# FA.net
KiCad netlist of a schematic drawn in EAGLE
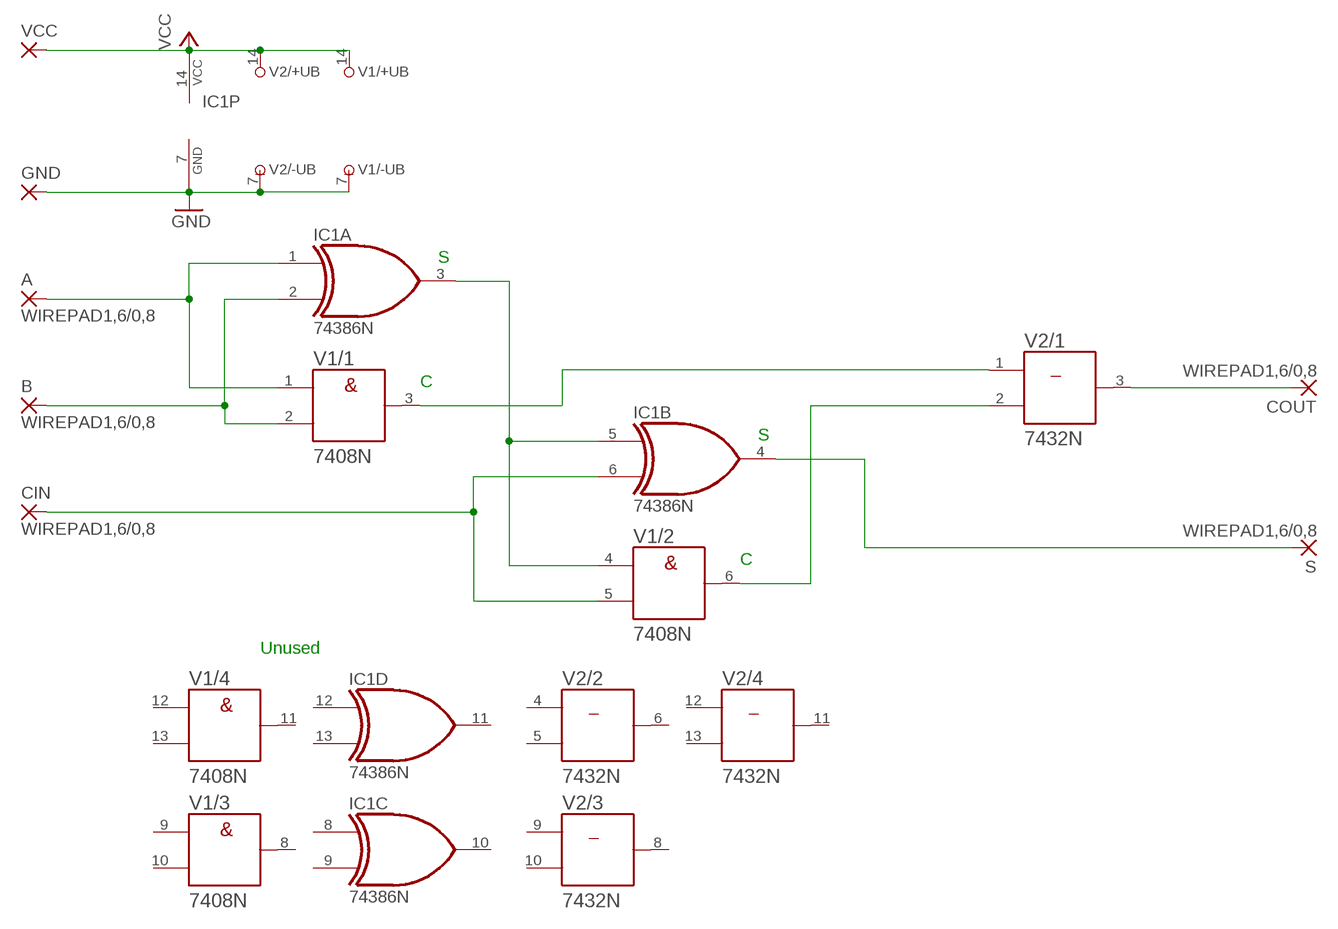
[diagram p0: schematic, sheet 1]

(export (version "E")
  (design (tool "Eeschema 10.0.6"))
  (components
    (comp (ref "A")
      (value "WIREPAD1,6/0,8")
      (footprint "eagle-import:1,6_0,8")
      (libsource (lib "eagle-import") (part "WIREPAD1,6/0,8"))
    )
    (comp (ref "B")
      (value "WIREPAD1,6/0,8")
      (footprint "eagle-import:1,6_0,8")
      (libsource (lib "eagle-import") (part "WIREPAD1,6/0,8"))
    )
    (comp (ref "CIN")
      (value "WIREPAD1,6/0,8")
      (footprint "eagle-import:1,6_0,8")
      (libsource (lib "eagle-import") (part "WIREPAD1,6/0,8"))
    )
    (comp (ref "COUT")
      (value "WIREPAD1,6/0,8")
      (footprint "eagle-import:1,6_0,8")
      (libsource (lib "eagle-import") (part "WIREPAD1,6/0,8"))
    )
    (comp (ref "GND")
      (value "1,6/0,8")
      (footprint "eagle-import:1,6_0,8")
      (libsource (lib "eagle-import") (part "1,6/0,8"))
    )
    (comp (ref "IC1")
      (value "74386N")
      (footprint "eagle-import:DIL14")
      (libsource (lib "eagle-import") (part "74386N"))
    )
    (comp (ref "S")
      (value "WIREPAD1,6/0,8")
      (footprint "eagle-import:1,6_0,8")
      (libsource (lib "eagle-import") (part "WIREPAD1,6/0,8"))
    )
    (comp (ref "V1")
      (value "7408N")
      (footprint "eagle-import:DIL14")
      (libsource (lib "eagle-import") (part "7408N"))
    )
    (comp (ref "V2")
      (value "7432N")
      (footprint "eagle-import:DIL14")
      (libsource (lib "eagle-import") (part "7432N"))
    )
    (comp (ref "VCC")
      (value "1,6/0,8")
      (footprint "eagle-import:1,6_0,8")
      (libsource (lib "eagle-import") (part "1,6/0,8"))
    )
  )
  (nets
    (net (code "1") (name "GND") (class "Default")
      (node (ref "GND") (pin "1") (pinfunction "P_1") (pintype "passive"))
      (node (ref "IC1") (pin "7") (pinfunction "GND_7") (pintype "power_in"))
      (node (ref "V1") (pin "7") (pinfunction "-UB_7") (pintype "power_in"))
      (node (ref "V2") (pin "7") (pinfunction "-UB_7") (pintype "power_in"))
    )
    (net (code "2") (name "Net-(A-P)") (class "Default")
      (node (ref "A") (pin "1") (pinfunction "P_1") (pintype "passive"))
      (node (ref "IC1") (pin "1") (pinfunction "I0_1") (pintype "input"))
      (node (ref "V1") (pin "1") (pinfunction "A_1") (pintype "input"))
    )
    (net (code "3") (name "Net-(B-P)") (class "Default")
      (node (ref "B") (pin "1") (pinfunction "P_1") (pintype "passive"))
      (node (ref "IC1") (pin "2") (pinfunction "I1_2") (pintype "input"))
      (node (ref "V1") (pin "2") (pinfunction "B_2") (pintype "input"))
    )
    (net (code "4") (name "Net-(CIN-P)") (class "Default")
      (node (ref "CIN") (pin "1") (pinfunction "P_1") (pintype "passive"))
      (node (ref "IC1") (pin "6") (pinfunction "I1_6") (pintype "input"))
      (node (ref "V1") (pin "5") (pinfunction "B_5") (pintype "input"))
    )
    (net (code "5") (name "Net-(COUT-P)") (class "Default")
      (node (ref "COUT") (pin "1") (pinfunction "P_1") (pintype "passive"))
      (node (ref "V2") (pin "3") (pinfunction "Y_3") (pintype "output"))
    )
    (net (code "6") (name "Net-(IC1A-O)") (class "Default")
      (node (ref "IC1") (pin "3") (pinfunction "O_3") (pintype "output"))
      (node (ref "IC1") (pin "5") (pinfunction "I0_5") (pintype "input"))
      (node (ref "V1") (pin "4") (pinfunction "A_4") (pintype "input"))
    )
    (net (code "7") (name "Net-(IC1B-O)") (class "Default")
      (node (ref "IC1") (pin "4") (pinfunction "O_4") (pintype "output"))
      (node (ref "S") (pin "1") (pinfunction "P_1") (pintype "passive"))
    )
    (net (code "8") (name "Net-(V1C-Y)") (class "Default")
      (node (ref "V1") (pin "3") (pinfunction "Y_3") (pintype "output"))
      (node (ref "V2") (pin "1") (pinfunction "A_1") (pintype "input"))
    )
    (net (code "9") (name "Net-(V1D-Y)") (class "Default")
      (node (ref "V1") (pin "6") (pinfunction "Y_6") (pintype "output"))
      (node (ref "V2") (pin "2") (pinfunction "B_2") (pintype "input"))
    )
    (net (code "10") (name "VCC") (class "Default")
      (node (ref "IC1") (pin "14") (pinfunction "VCC_14") (pintype "power_in"))
      (node (ref "V1") (pin "14") (pinfunction "+UB_14") (pintype "power_in"))
      (node (ref "V2") (pin "14") (pinfunction "+UB_14") (pintype "power_in"))
      (node (ref "VCC") (pin "1") (pinfunction "P_1") (pintype "passive"))
    )
    (net (code "11") (name "unconnected-(IC1C-I0-Pad8)") (class "Default")
      (node (ref "IC1") (pin "8") (pinfunction "I0_8") (pintype "input"))
    )
    (net (code "12") (name "unconnected-(IC1C-I1-Pad9)") (class "Default")
      (node (ref "IC1") (pin "9") (pinfunction "I1_9") (pintype "input"))
    )
    (net (code "13") (name "unconnected-(IC1C-O-Pad10)") (class "Default")
      (node (ref "IC1") (pin "10") (pinfunction "O_10") (pintype "output"))
    )
    (net (code "14") (name "unconnected-(IC1D-I0-Pad12)") (class "Default")
      (node (ref "IC1") (pin "12") (pinfunction "I0_12") (pintype "input"))
    )
    (net (code "15") (name "unconnected-(IC1D-I1-Pad13)") (class "Default")
      (node (ref "IC1") (pin "13") (pinfunction "I1_13") (pintype "input"))
    )
    (net (code "16") (name "unconnected-(IC1D-O-Pad11)") (class "Default")
      (node (ref "IC1") (pin "11") (pinfunction "O_11") (pintype "output"))
    )
    (net (code "17") (name "unconnected-(V1E-A-Pad9)") (class "Default")
      (node (ref "V1") (pin "9") (pinfunction "A_9") (pintype "input"))
    )
    (net (code "18") (name "unconnected-(V1E-B-Pad10)") (class "Default")
      (node (ref "V1") (pin "10") (pinfunction "B_10") (pintype "input"))
    )
    (net (code "19") (name "unconnected-(V1E-Y-Pad8)") (class "Default")
      (node (ref "V1") (pin "8") (pinfunction "Y_8") (pintype "output"))
    )
    (net (code "20") (name "unconnected-(V1F-A-Pad12)") (class "Default")
      (node (ref "V1") (pin "12") (pinfunction "A_12") (pintype "input"))
    )
    (net (code "21") (name "unconnected-(V1F-B-Pad13)") (class "Default")
      (node (ref "V1") (pin "13") (pinfunction "B_13") (pintype "input"))
    )
    (net (code "22") (name "unconnected-(V1F-Y-Pad11)") (class "Default")
      (node (ref "V1") (pin "11") (pinfunction "Y_11") (pintype "output"))
    )
    (net (code "23") (name "unconnected-(V2D-A-Pad4)") (class "Default")
      (node (ref "V2") (pin "4") (pinfunction "A_4") (pintype "input"))
    )
    (net (code "24") (name "unconnected-(V2D-B-Pad5)") (class "Default")
      (node (ref "V2") (pin "5") (pinfunction "B_5") (pintype "input"))
    )
    (net (code "25") (name "unconnected-(V2D-Y-Pad6)") (class "Default")
      (node (ref "V2") (pin "6") (pinfunction "Y_6") (pintype "output"))
    )
    (net (code "26") (name "unconnected-(V2E-A-Pad9)") (class "Default")
      (node (ref "V2") (pin "9") (pinfunction "A_9") (pintype "input"))
    )
    (net (code "27") (name "unconnected-(V2E-B-Pad10)") (class "Default")
      (node (ref "V2") (pin "10") (pinfunction "B_10") (pintype "input"))
    )
    (net (code "28") (name "unconnected-(V2E-Y-Pad8)") (class "Default")
      (node (ref "V2") (pin "8") (pinfunction "Y_8") (pintype "output"))
    )
    (net (code "29") (name "unconnected-(V2F-A-Pad12)") (class "Default")
      (node (ref "V2") (pin "12") (pinfunction "A_12") (pintype "input"))
    )
    (net (code "30") (name "unconnected-(V2F-B-Pad13)") (class "Default")
      (node (ref "V2") (pin "13") (pinfunction "B_13") (pintype "input"))
    )
    (net (code "31") (name "unconnected-(V2F-Y-Pad11)") (class "Default")
      (node (ref "V2") (pin "11") (pinfunction "Y_11") (pintype "output"))
    )
  )
)
